# quickpi.net
KiCad netlist of a schematic drawn in EAGLE
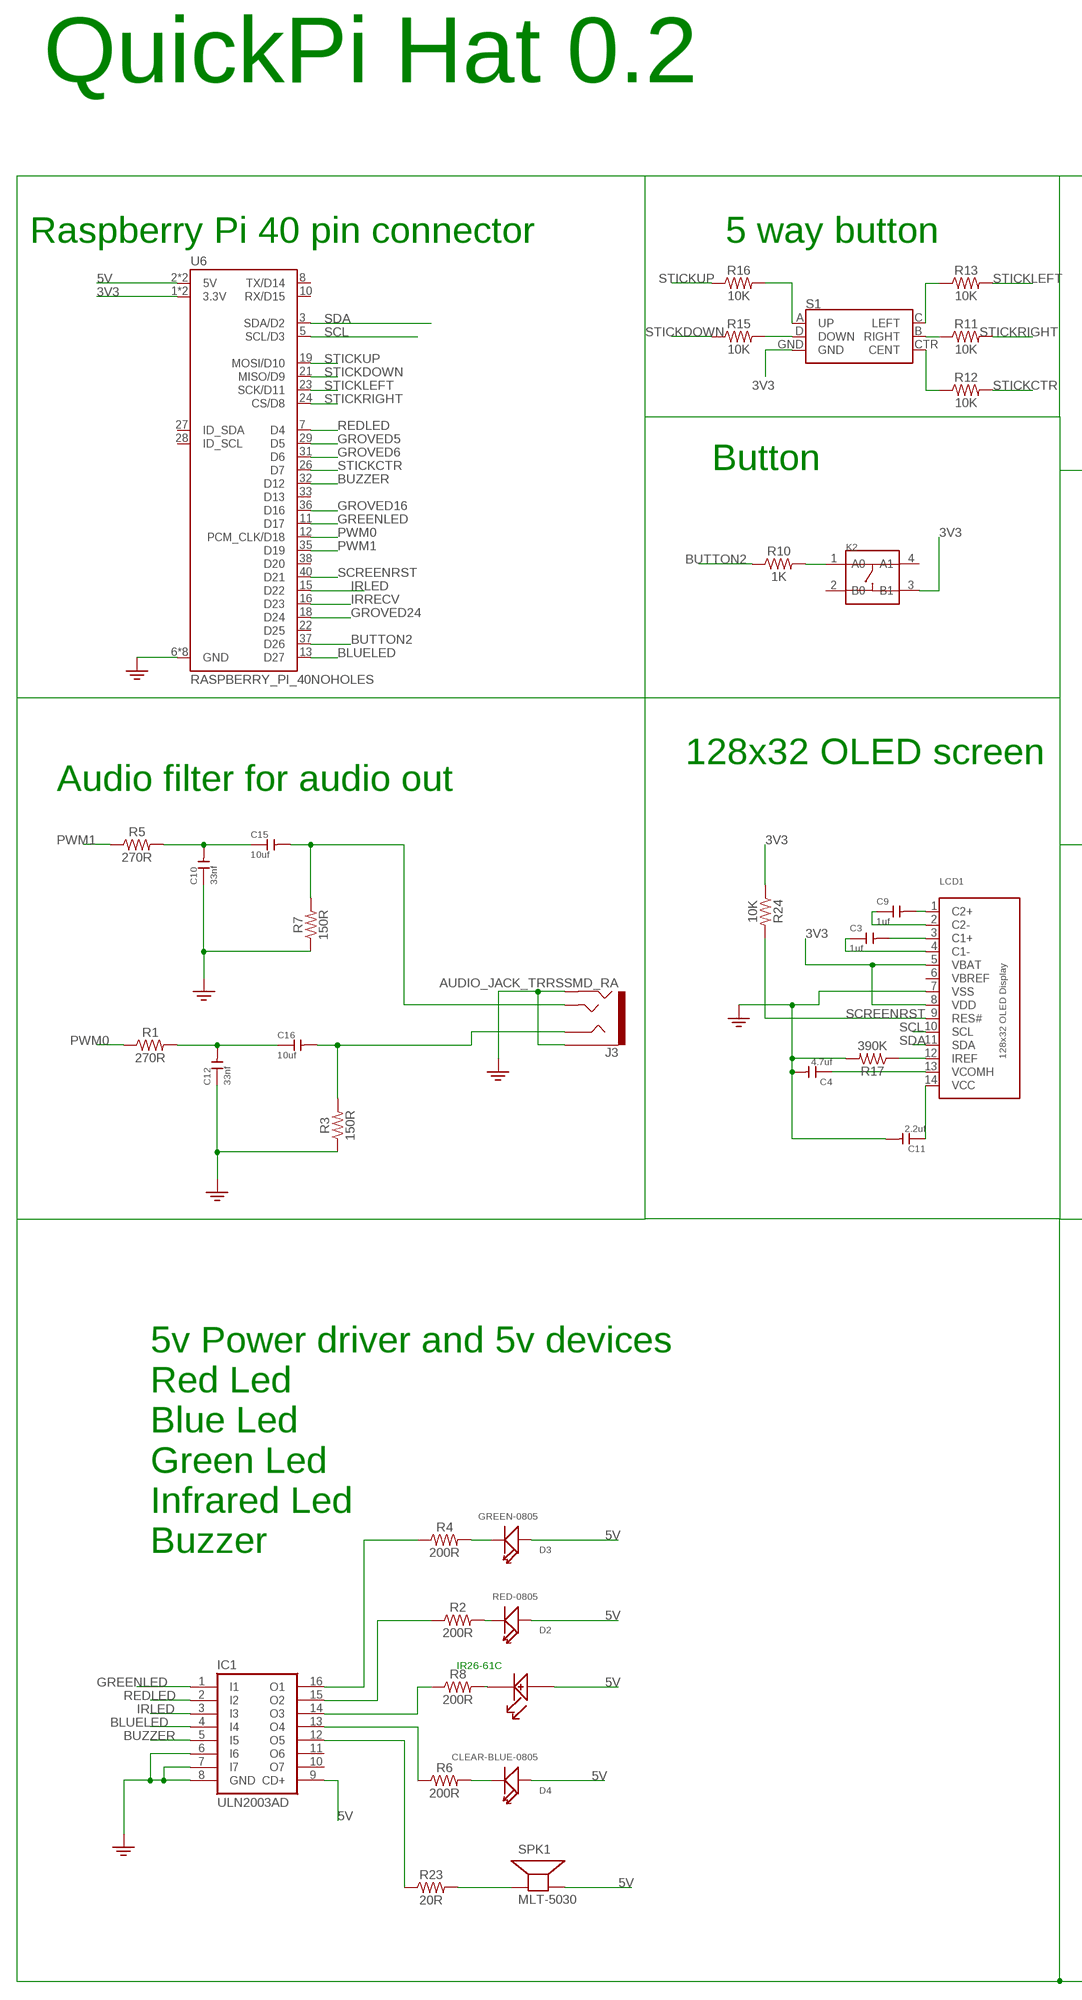
[diagram p0: schematic, sheet 1, part 1 of 2]
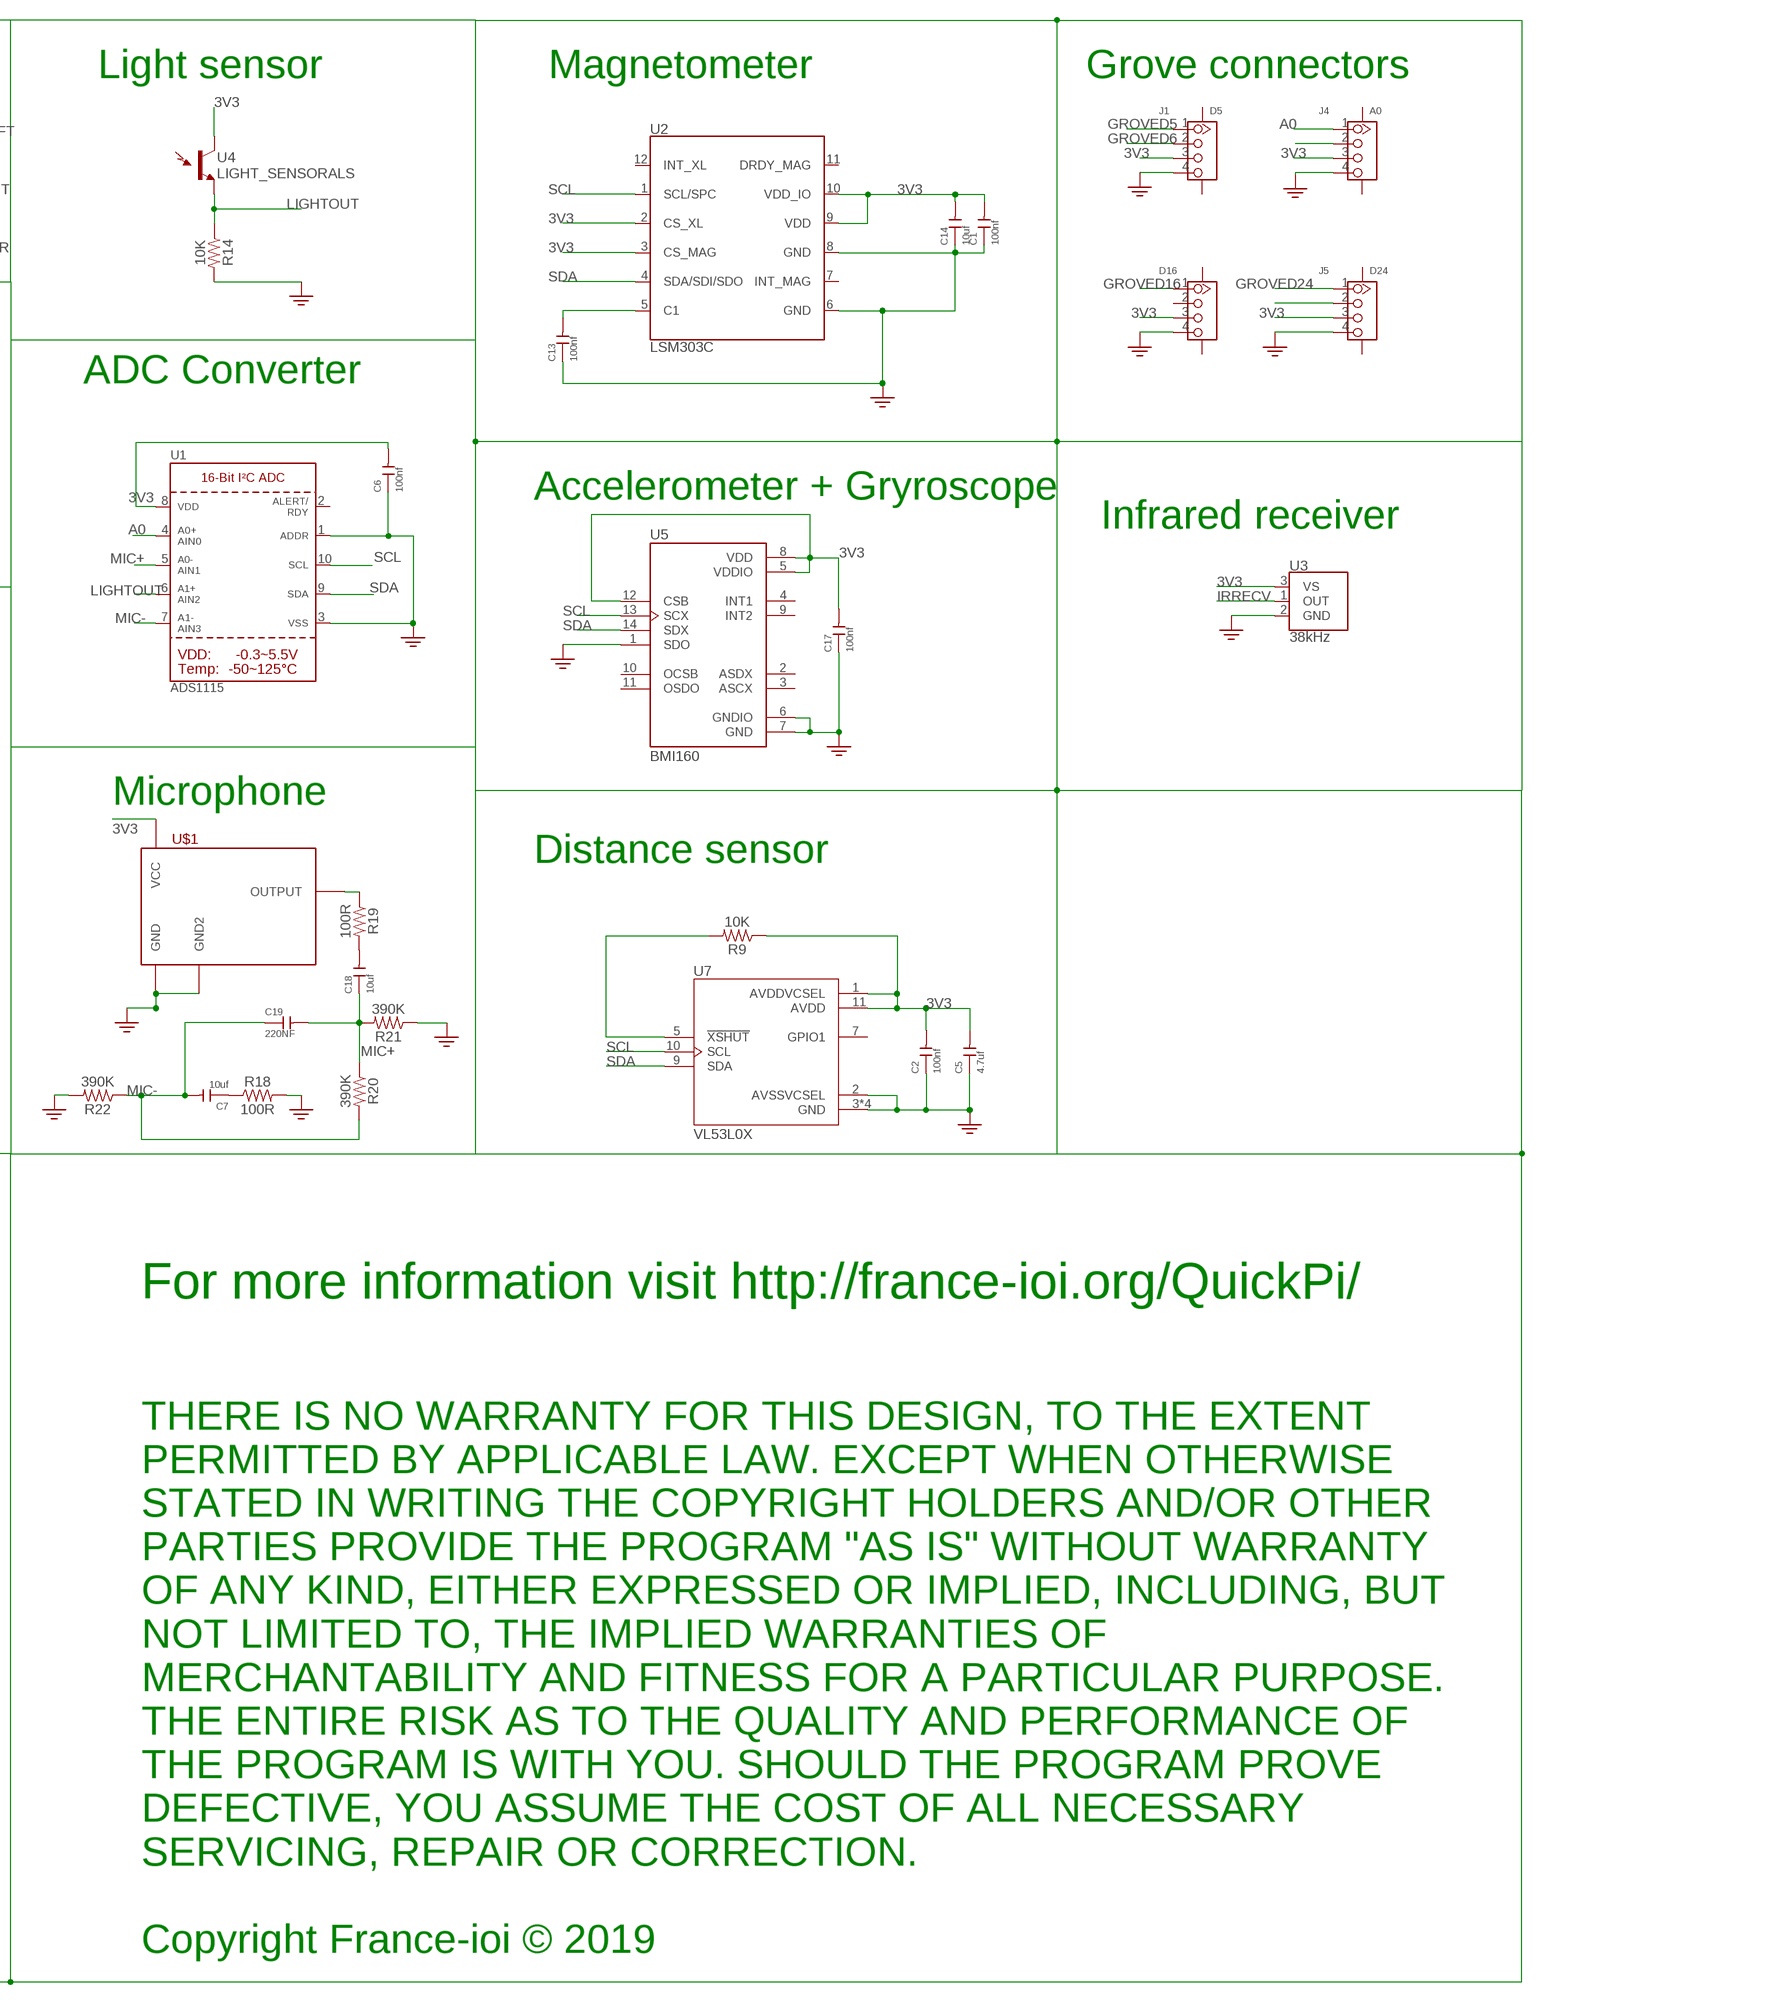
[diagram p1: schematic, sheet 1, part 2 of 2]

(export (version "E")
  (design (tool "Eeschema 10.0.6"))
  (components
    (comp (ref "C1")
      (value "100nf")
      (footprint "eagle-import:C0402")
      (fields (field (name "MPN") "CC0402KRX7R8BB104"))
      (libsource (lib "eagle-import") (part "CERAMIC-100NF-25V-10%-X7R(0402)"))
    )
    (comp (ref "C2")
      (value "100nf")
      (footprint "eagle-import:C0402")
      (fields (field (name "MPN") "CC0402KRX7R8BB104"))
      (libsource (lib "eagle-import") (part "CERAMIC-100NF-25V-10%-X7R(0402)"))
    )
    (comp (ref "C3")
      (value "1uf")
      (footprint "eagle-import:C0402")
      (fields (field (name "MPN") "CC0402KRX5R6BB105"))
      (libsource (lib "eagle-import") (part "CERAMIC-1UF-10V-10%-X5R(0402)"))
    )
    (comp (ref "C4")
      (value "4.7uf")
      (footprint "eagle-import:C0402")
      (fields (field (name "MPN") "CC0402MRX5R5BB475"))
      (libsource (lib "eagle-import") (part "CERAMIC-4.7UF-6.3V-20%-X5R(0402)"))
    )
    (comp (ref "C5")
      (value "4.7uf")
      (footprint "eagle-import:C0402")
      (fields (field (name "MPN") "CC0402MRX5R5BB475"))
      (libsource (lib "eagle-import") (part "CERAMIC-4.7UF-6.3V-20%-X5R(0402)"))
    )
    (comp (ref "C6")
      (value "100nf")
      (footprint "eagle-import:C0402")
      (fields (field (name "MPN") "CC0402KRX7R8BB104"))
      (libsource (lib "eagle-import") (part "CERAMIC-100NF-25V-10%-X7R(0402)"))
    )
    (comp (ref "C7")
      (value "10uf")
      (footprint "eagle-import:C0402")
      (fields (field (name "MPN") "CC0402KRX5R6BB105"))
      (libsource (lib "eagle-import") (part "CERAMIC-1UF-10V-10%-X5R(0402)"))
    )
    (comp (ref "C9")
      (value "1uf")
      (footprint "eagle-import:C0402")
      (fields (field (name "MPN") "CC0402KRX5R6BB105"))
      (libsource (lib "eagle-import") (part "CERAMIC-1UF-10V-10%-X5R(0402)"))
    )
    (comp (ref "C10")
      (value "33nf")
      (footprint "eagle-import:C0402")
      (fields (field (name "MPN") "CC0402MRX5R5BB106"))
      (libsource (lib "eagle-import") (part "CERAMIC-10UF-6.3V-20%-X5R(0402)"))
    )
    (comp (ref "C11")
      (value "2.2uf")
      (footprint "eagle-import:C0402")
      (fields (field (name "MPN") "CC0402MRX5R5BB475"))
      (libsource (lib "eagle-import") (part "CERAMIC-4.7UF-6.3V-20%-X5R(0402)"))
    )
    (comp (ref "C12")
      (value "33nf")
      (footprint "eagle-import:C0402")
      (fields (field (name "MPN") "CC0402MRX5R5BB106"))
      (libsource (lib "eagle-import") (part "CERAMIC-10UF-6.3V-20%-X5R(0402)"))
    )
    (comp (ref "C13")
      (value "100nf")
      (footprint "eagle-import:C0402")
      (fields (field (name "MPN") "CC0402KRX7R8BB104"))
      (libsource (lib "eagle-import") (part "CERAMIC-100NF-25V-10%-X7R(0402)"))
    )
    (comp (ref "C14")
      (value "10uf")
      (footprint "eagle-import:C0402")
      (fields (field (name "MPN") "CC0402MRX5R5BB106"))
      (libsource (lib "eagle-import") (part "CERAMIC-10UF-6.3V-20%-X5R(0402)"))
    )
    (comp (ref "C15")
      (value "10uf")
      (footprint "eagle-import:C0402")
      (fields (field (name "MPN") "CC0402MRX5R5BB106"))
      (libsource (lib "eagle-import") (part "CERAMIC-10UF-6.3V-20%-X5R(0402)"))
    )
    (comp (ref "C16")
      (value "10uf")
      (footprint "eagle-import:C0402")
      (fields (field (name "MPN") "CC0402MRX5R5BB106"))
      (libsource (lib "eagle-import") (part "CERAMIC-10UF-6.3V-20%-X5R(0402)"))
    )
    (comp (ref "C17")
      (value "100nf")
      (footprint "eagle-import:C0402")
      (fields (field (name "MPN") "CC0402KRX7R8BB104"))
      (libsource (lib "eagle-import") (part "CERAMIC-100NF-25V-10%-X7R(0402)"))
    )
    (comp (ref "C18")
      (value "10uf")
      (footprint "eagle-import:C0402")
      (fields (field (name "MPN") "CC0402KRX5R6BB105"))
      (libsource (lib "eagle-import") (part "CERAMIC-1UF-10V-10%-X5R(0402)"))
    )
    (comp (ref "C19")
      (value "220NF")
      (footprint "eagle-import:C0402")
      (fields (field (name "MPN") "CC0402KRX7R7BB224"))
      (libsource (lib "eagle-import") (part "CERAMIC-220NF-16V-10%-X7R(0402)"))
    )
    (comp (ref "D2")
      (value "RED-0805")
      (footprint "eagle-import:LED-0805")
      (fields (field (name "MPN") "17-215SURC/S530-A2/TR8"))
      (libsource (lib "eagle-import") (part "SMD-LED-CLEAR-RED(0805)"))
    )
    (comp (ref "D3")
      (value "GREEN-0805")
      (footprint "eagle-import:LED-0805")
      (fields (field (name "MPN") "17-215SYGC/S530-E2/TR8"))
      (libsource (lib "eagle-import") (part "SMD-LED-CLEAR-GREEN(0805)"))
    )
    (comp (ref "D4")
      (value "CLEAR-BLUE-0805")
      (footprint "eagle-import:LED-0805")
      (fields (field (name "MPN") "EL-17-215/BHC-AN1P2/3T"))
      (libsource (lib "eagle-import") (part "SMD-LED-CLEAR-BLUE(0805)"))
    )
    (comp (ref "D16")
      (value "GROVE-CONNECTOR-SMD-90D(4+2P-2.0)")
      (footprint "eagle-import:HW4-SMD-2.0-90D")
      (libsource (lib "eagle-import") (part "GROVE-CONNECTOR-SMD-90D(4+2P-2.0)"))
    )
    (comp (ref "IC1")
      (value "ULN2003AD")
      (footprint "eagle-import:SO16")
      (libsource (lib "eagle-import") (part "ULN2003AD"))
    )
    (comp (ref "J1")
      (value "D5")
      (footprint "eagle-import:HW4-SMD-2.0-90D")
      (libsource (lib "eagle-import") (part "GROVE-CONNECTOR-SMD-90D(4+2P-2.0)"))
    )
    (comp (ref "J3")
      (value "AUDIO_JACK_TRRSSMD_RA")
      (footprint "eagle-import:AUDIO_JACK_3.5MM_TRRS_SMD_RA")
      (libsource (lib "eagle-import") (part "AUDIO_JACK_TRRSSMD_RA"))
    )
    (comp (ref "J4")
      (value "A0")
      (footprint "eagle-import:HW4-SMD-2.0-90D")
      (libsource (lib "eagle-import") (part "GROVE-CONNECTOR-SMD-90D(4+2P-2.0)"))
    )
    (comp (ref "J5")
      (value "D24")
      (footprint "eagle-import:HW4-SMD-2.0-90D")
      (libsource (lib "eagle-import") (part "GROVE-CONNECTOR-SMD-90D(4+2P-2.0)"))
    )
    (comp (ref "K2")
      (value "SMD-SWITCH-TACTILE-SPST-NO(4P-D6.0MM)")
      (footprint "eagle-import:SW4-SMD-6.0X6.0X5.0MM")
      (fields (field (name "MPN") "DTSM-62K-S-V-T/R(SN431)"))
      (libsource (lib "eagle-import") (part "SMD-SWITCH-TACTILE-SPST-NO(4P-D6.0MM)"))
    )
    (comp (ref "LCD1")
      (value "DISP_OLED_UG-2832HSWEG02")
      (footprint "eagle-import:UG-2832HSWEG02_WRAPUNDER")
      (libsource (lib "eagle-import") (part "DISP_OLED_UG-2832HSWEG02"))
    )
    (comp (ref "R1")
      (value "270R")
      (footprint "eagle-import:0402")
      (libsource (lib "eagle-import") (part "RESISTOR0402"))
    )
    (comp (ref "R2")
      (value "200R")
      (footprint "eagle-import:0402")
      (libsource (lib "eagle-import") (part "RESISTOR0402"))
    )
    (comp (ref "R3")
      (value "150R")
      (footprint "eagle-import:0402")
      (libsource (lib "eagle-import") (part "RESISTOR0402"))
    )
    (comp (ref "R4")
      (value "200R")
      (footprint "eagle-import:0402")
      (libsource (lib "eagle-import") (part "RESISTOR0402"))
    )
    (comp (ref "R5")
      (value "270R")
      (footprint "eagle-import:0402")
      (libsource (lib "eagle-import") (part "RESISTOR0402"))
    )
    (comp (ref "R6")
      (value "200R")
      (footprint "eagle-import:0402")
      (libsource (lib "eagle-import") (part "RESISTOR0402"))
    )
    (comp (ref "R7")
      (value "150R")
      (footprint "eagle-import:0402")
      (libsource (lib "eagle-import") (part "RESISTOR0402"))
    )
    (comp (ref "R8")
      (value "200R")
      (footprint "eagle-import:0402")
      (libsource (lib "eagle-import") (part "RESISTOR0402"))
    )
    (comp (ref "R9")
      (value "10K")
      (footprint "eagle-import:0402")
      (libsource (lib "eagle-import") (part "RESISTOR0402"))
    )
    (comp (ref "R10")
      (value "1K")
      (footprint "eagle-import:0402")
      (libsource (lib "eagle-import") (part "RESISTOR0402"))
    )
    (comp (ref "R11")
      (value "10K")
      (footprint "eagle-import:0402")
      (libsource (lib "eagle-import") (part "RESISTOR0402"))
    )
    (comp (ref "R12")
      (value "10K")
      (footprint "eagle-import:0402")
      (libsource (lib "eagle-import") (part "RESISTOR0402"))
    )
    (comp (ref "R13")
      (value "10K")
      (footprint "eagle-import:0402")
      (libsource (lib "eagle-import") (part "RESISTOR0402"))
    )
    (comp (ref "R14")
      (value "10K")
      (footprint "eagle-import:0402")
      (libsource (lib "eagle-import") (part "RESISTOR0402"))
    )
    (comp (ref "R15")
      (value "10K")
      (footprint "eagle-import:0402")
      (libsource (lib "eagle-import") (part "RESISTOR0402"))
    )
    (comp (ref "R16")
      (value "10K")
      (footprint "eagle-import:0402")
      (libsource (lib "eagle-import") (part "RESISTOR0402"))
    )
    (comp (ref "R17")
      (value "390K")
      (footprint "eagle-import:0402")
      (libsource (lib "eagle-import") (part "RESISTOR0402"))
    )
    (comp (ref "R18")
      (value "100R")
      (footprint "eagle-import:0402")
      (libsource (lib "eagle-import") (part "RESISTOR0402"))
    )
    (comp (ref "R19")
      (value "100R")
      (footprint "eagle-import:0402")
      (libsource (lib "eagle-import") (part "RESISTOR0402"))
    )
    (comp (ref "R20")
      (value "390K")
      (footprint "eagle-import:0402")
      (libsource (lib "eagle-import") (part "RESISTOR0402"))
    )
    (comp (ref "R21")
      (value "390K")
      (footprint "eagle-import:0402")
      (libsource (lib "eagle-import") (part "RESISTOR0402"))
    )
    (comp (ref "R22")
      (value "390K")
      (footprint "eagle-import:0402")
      (libsource (lib "eagle-import") (part "RESISTOR0402"))
    )
    (comp (ref "R23")
      (value "20R")
      (footprint "eagle-import:0402")
      (libsource (lib "eagle-import") (part "RESISTOR0402"))
    )
    (comp (ref "R24")
      (value "10K")
      (footprint "eagle-import:0402")
      (libsource (lib "eagle-import") (part "RESISTOR0402"))
    )
    (comp (ref "S1")
      (value "JOYSTICK_MINI")
      (footprint "eagle-import:JOYSTICK_MINI")
      (libsource (lib "eagle-import") (part "JOYSTICK_MINI"))
    )
    (comp (ref "SPK1")
      (value "MLT-5030")
      (footprint "eagle-import:SMT-0540-S-R")
      (libsource (lib "eagle-import") (part "SMT-0540-S-R"))
    )
    (comp (ref "U$1")
      (value "MEMS_MIC_SPU0414HR5H-SB")
      (footprint "eagle-import:CSP-4PIN")
      (libsource (lib "eagle-import") (part "MEMS_MIC_SPU0414HR5H-SB"))
    )
    (comp (ref "U$2")
      (value "IR26-61C/L302/TR8")
      (footprint "eagle-import:IR26-61C_L302_TR8")
      (libsource (lib "eagle-import") (part "IR26-61C/L302/TR8"))
    )
    (comp (ref "U1")
      (value "ADS1015")
      (footprint "eagle-import:MSOP10")
      (fields (field (name "MF") "Texas Instruments") (field (name "MP") "ADS1115"))
      (libsource (lib "eagle-import") (part "ADS1115"))
    )
    (comp (ref "U2")
      (value "LSM303C")
      (footprint "eagle-import:LGA-12")
      (libsource (lib "eagle-import") (part "LSM303C"))
    )
    (comp (ref "U3")
      (value "38kHz")
      (footprint "eagle-import:TSOP382")
      (libsource (lib "eagle-import") (part "TSOP38238"))
    )
    (comp (ref "U4")
      (value "LIGHT_SENSORALS")
      (footprint "eagle-import:ALS-PT19")
      (libsource (lib "eagle-import") (part "LIGHT_SENSORALS"))
    )
    (comp (ref "U5")
      (value "BMI160")
      (footprint "eagle-import:PQFN50P300X250X88-14N")
      (fields (field (name "MF") "Bosch"))
      (libsource (lib "eagle-import") (part "BMI160"))
    )
    (comp (ref "U6")
      (value "RASPBERRY_PI_40NOHOLES")
      (footprint "eagle-import:RASPBERRY_PI_SHIELD_NOHOLES")
      (libsource (lib "eagle-import") (part "RASPBERRY_PI_40NOHOLES"))
    )
    (comp (ref "U7")
      (value "VL53L0X")
      (footprint "eagle-import:SENSOR_VL53L0X")
      (fields (field (name "MF") "STMicroelectronics"))
      (libsource (lib "eagle-import") (part "VL53L0X"))
    )
  )
  (nets
    (net (code "1") (name "/3V3") (class "Default")
      (node (ref "C1") (pin "2") (pinfunction "2_2") (pintype "passive"))
      (node (ref "C14") (pin "2") (pinfunction "2_2") (pintype "passive"))
      (node (ref "C17") (pin "2") (pinfunction "2_2") (pintype "passive"))
      (node (ref "C2") (pin "2") (pinfunction "2_2") (pintype "passive"))
      (node (ref "C5") (pin "2") (pinfunction "2_2") (pintype "passive"))
      (node (ref "C6") (pin "2") (pinfunction "2_2") (pintype "passive"))
      (node (ref "D16") (pin "3") (pinfunction "3_3") (pintype "bidirectional"))
      (node (ref "J1") (pin "3") (pinfunction "3_3") (pintype "bidirectional"))
      (node (ref "J4") (pin "3") (pinfunction "3_3") (pintype "bidirectional"))
      (node (ref "J5") (pin "3") (pinfunction "3_3") (pintype "bidirectional"))
      (node (ref "K2") (pin "3") (pinfunction "B1_3") (pintype "bidirectional"))
      (node (ref "LCD1") (pin "5") (pinfunction "VBAT_5") (pintype "power_in"))
      (node (ref "LCD1") (pin "8") (pinfunction "VDD_8") (pintype "power_in"))
      (node (ref "R24") (pin "1") (pinfunction "1_1") (pintype "passive"))
      (node (ref "R9") (pin "1") (pinfunction "1_1") (pintype "passive"))
      (node (ref "S1") (pin "GND") (pinfunction "GND_GND") (pintype "bidirectional"))
      (node (ref "U$1") (pin "VCC") (pinfunction "VCC_VCC") (pintype "bidirectional"))
      (node (ref "U1") (pin "8") (pinfunction "VDD_8") (pintype "bidirectional"))
      (node (ref "U2") (pin "10") (pinfunction "VDD_IO_10") (pintype "bidirectional"))
      (node (ref "U2") (pin "2") (pinfunction "CS_XL_2") (pintype "bidirectional"))
      (node (ref "U2") (pin "3") (pinfunction "CS_MAG_3") (pintype "bidirectional"))
      (node (ref "U2") (pin "9") (pinfunction "VDD_9") (pintype "bidirectional"))
      (node (ref "U3") (pin "3") (pinfunction "VS_3") (pintype "bidirectional"))
      (node (ref "U4") (pin "C") (pinfunction "C1_C") (pintype "passive"))
      (node (ref "U5") (pin "12") (pinfunction "CSB_12") (pintype "input"))
      (node (ref "U5") (pin "5") (pinfunction "VDDIO_5") (pintype "power_in"))
      (node (ref "U5") (pin "8") (pinfunction "VDD_8") (pintype "power_in"))
      (node (ref "U6") (pin "1") (pinfunction "3.3V_1") (pintype "bidirectional"))
      (node (ref "U6") (pin "17") (pinfunction "3.3V_17") (pintype "bidirectional"))
      (node (ref "U7") (pin "1") (pinfunction "AVDDVCSEL_1") (pintype "power_in"))
      (node (ref "U7") (pin "11") (pinfunction "AVDD_11") (pintype "power_in"))
    )
    (net (code "2") (name "/5V") (class "Default")
      (node (ref "D2") (pin "+") (pinfunction "+_+") (pintype "passive"))
      (node (ref "D3") (pin "+") (pinfunction "+_+") (pintype "passive"))
      (node (ref "D4") (pin "+") (pinfunction "+_+") (pintype "passive"))
      (node (ref "IC1") (pin "9") (pinfunction "CD+_9") (pintype "passive"))
      (node (ref "SPK1") (pin "+") (pinfunction "-_+") (pintype "passive"))
      (node (ref "U$2") (pin "VCC") (pinfunction "GND_VCC") (pintype "bidirectional"))
      (node (ref "U6") (pin "2") (pinfunction "5V_2") (pintype "bidirectional"))
      (node (ref "U6") (pin "4") (pinfunction "5V_4") (pintype "bidirectional"))
    )
    (net (code "3") (name "/A0") (class "Default")
      (node (ref "J4") (pin "1") (pinfunction "1_1") (pintype "bidirectional"))
      (node (ref "U1") (pin "4") (pinfunction "AIN0_4") (pintype "bidirectional"))
    )
    (net (code "4") (name "/BLUELED") (class "Default")
      (node (ref "IC1") (pin "4") (pinfunction "I4_4") (pintype "input"))
      (node (ref "U6") (pin "13") (pinfunction "D27_13") (pintype "bidirectional"))
    )
    (net (code "5") (name "/BUTTON2") (class "Default")
      (node (ref "R10") (pin "1") (pinfunction "1_1") (pintype "passive"))
      (node (ref "U6") (pin "37") (pinfunction "D26_37") (pintype "bidirectional"))
    )
    (net (code "6") (name "/BUZZER") (class "Default")
      (node (ref "IC1") (pin "5") (pinfunction "I5_5") (pintype "input"))
      (node (ref "U6") (pin "32") (pinfunction "D12_32") (pintype "bidirectional"))
    )
    (net (code "7") (name "/GREENLED") (class "Default")
      (node (ref "IC1") (pin "1") (pinfunction "I1_1") (pintype "input"))
      (node (ref "U6") (pin "11") (pinfunction "D17_11") (pintype "bidirectional"))
    )
    (net (code "8") (name "/GROVED5") (class "Default")
      (node (ref "J1") (pin "1") (pinfunction "1_1") (pintype "bidirectional"))
      (node (ref "U6") (pin "29") (pinfunction "D5_29") (pintype "bidirectional"))
    )
    (net (code "9") (name "/GROVED6") (class "Default")
      (node (ref "J1") (pin "2") (pinfunction "2_2") (pintype "bidirectional"))
      (node (ref "U6") (pin "31") (pinfunction "D6_31") (pintype "bidirectional"))
    )
    (net (code "10") (name "/GROVED16") (class "Default")
      (node (ref "D16") (pin "1") (pinfunction "1_1") (pintype "bidirectional"))
      (node (ref "U6") (pin "36") (pinfunction "D16_36") (pintype "bidirectional"))
    )
    (net (code "11") (name "/GROVED24") (class "Default")
      (node (ref "J5") (pin "1") (pinfunction "1_1") (pintype "bidirectional"))
      (node (ref "U6") (pin "18") (pinfunction "D24_18") (pintype "bidirectional"))
    )
    (net (code "12") (name "/IRLED") (class "Default")
      (node (ref "IC1") (pin "3") (pinfunction "I3_3") (pintype "input"))
      (node (ref "U6") (pin "15") (pinfunction "D22_15") (pintype "bidirectional"))
    )
    (net (code "13") (name "/IRRECV") (class "Default")
      (node (ref "U3") (pin "1") (pinfunction "OUT_1") (pintype "bidirectional"))
      (node (ref "U6") (pin "16") (pinfunction "D23_16") (pintype "bidirectional"))
    )
    (net (code "14") (name "/LIGHTOUT") (class "Default")
      (node (ref "R14") (pin "1") (pinfunction "1_1") (pintype "passive"))
      (node (ref "U1") (pin "6") (pinfunction "AIN2_6") (pintype "bidirectional"))
      (node (ref "U4") (pin "E") (pinfunction "E1_E") (pintype "passive"))
    )
    (net (code "15") (name "/MIC+") (class "Default")
      (node (ref "C18") (pin "1") (pinfunction "1_1") (pintype "passive"))
      (node (ref "C19") (pin "2") (pinfunction "2_2") (pintype "passive"))
      (node (ref "R20") (pin "1") (pinfunction "1_1") (pintype "passive"))
      (node (ref "R21") (pin "2") (pinfunction "2_2") (pintype "passive"))
      (node (ref "U1") (pin "5") (pinfunction "AIN1_5") (pintype "bidirectional"))
    )
    (net (code "16") (name "/MIC-") (class "Default")
      (node (ref "C19") (pin "1") (pinfunction "1_1") (pintype "passive"))
      (node (ref "C7") (pin "2") (pinfunction "2_2") (pintype "passive"))
      (node (ref "R20") (pin "2") (pinfunction "2_2") (pintype "passive"))
      (node (ref "R22") (pin "1") (pinfunction "1_1") (pintype "passive"))
      (node (ref "U1") (pin "7") (pinfunction "AIN3_7") (pintype "bidirectional"))
    )
    (net (code "17") (name "/PWM0") (class "Default")
      (node (ref "R1") (pin "1") (pinfunction "1_1") (pintype "passive"))
      (node (ref "U6") (pin "12") (pinfunction "PCM_CLK/D18_12") (pintype "bidirectional"))
    )
    (net (code "18") (name "/PWM1") (class "Default")
      (node (ref "R5") (pin "1") (pinfunction "1_1") (pintype "passive"))
      (node (ref "U6") (pin "35") (pinfunction "D19_35") (pintype "bidirectional"))
    )
    (net (code "19") (name "/REDLED") (class "Default")
      (node (ref "IC1") (pin "2") (pinfunction "I2_2") (pintype "input"))
      (node (ref "U6") (pin "7") (pinfunction "D4_7") (pintype "bidirectional"))
    )
    (net (code "20") (name "/SCL") (class "Default")
      (node (ref "LCD1") (pin "10") (pinfunction "SCL_10") (pintype "bidirectional"))
      (node (ref "U1") (pin "10") (pinfunction "SCL_10") (pintype "bidirectional"))
      (node (ref "U2") (pin "1") (pinfunction "SCL/SPC_1") (pintype "bidirectional"))
      (node (ref "U5") (pin "13") (pinfunction "SCX_13") (pintype "input"))
      (node (ref "U6") (pin "5") (pinfunction "SCL/D3_5") (pintype "bidirectional"))
      (node (ref "U7") (pin "10") (pinfunction "SCL_10") (pintype "input"))
    )
    (net (code "21") (name "/SCREENRST") (class "Default")
      (node (ref "LCD1") (pin "9") (pinfunction "RES#_9") (pintype "bidirectional"))
      (node (ref "R24") (pin "2") (pinfunction "2_2") (pintype "passive"))
      (node (ref "U6") (pin "40") (pinfunction "D21_40") (pintype "bidirectional"))
    )
    (net (code "22") (name "/SDA") (class "Default")
      (node (ref "LCD1") (pin "11") (pinfunction "SDA_11") (pintype "bidirectional"))
      (node (ref "U1") (pin "9") (pinfunction "SDA_9") (pintype "bidirectional"))
      (node (ref "U2") (pin "4") (pinfunction "SDA/SDI/SDO_4") (pintype "bidirectional"))
      (node (ref "U5") (pin "14") (pinfunction "SDX_14") (pintype "bidirectional"))
      (node (ref "U6") (pin "3") (pinfunction "SDA/D2_3") (pintype "bidirectional"))
      (node (ref "U7") (pin "9") (pinfunction "SDA_9") (pintype "bidirectional"))
    )
    (net (code "23") (name "/STICKCTR") (class "Default")
      (node (ref "R12") (pin "2") (pinfunction "2_2") (pintype "passive"))
      (node (ref "U6") (pin "26") (pinfunction "D7_26") (pintype "bidirectional"))
    )
    (net (code "24") (name "/STICKDOWN") (class "Default")
      (node (ref "R15") (pin "1") (pinfunction "1_1") (pintype "passive"))
      (node (ref "U6") (pin "21") (pinfunction "MISO/D9_21") (pintype "bidirectional"))
    )
    (net (code "25") (name "/STICKLEFT") (class "Default")
      (node (ref "R13") (pin "2") (pinfunction "2_2") (pintype "passive"))
      (node (ref "U6") (pin "23") (pinfunction "SCK/D11_23") (pintype "bidirectional"))
    )
    (net (code "26") (name "/STICKRIGHT") (class "Default")
      (node (ref "R11") (pin "2") (pinfunction "2_2") (pintype "passive"))
      (node (ref "U6") (pin "24") (pinfunction "CS/D8_24") (pintype "bidirectional"))
    )
    (net (code "27") (name "/STICKUP") (class "Default")
      (node (ref "R16") (pin "1") (pinfunction "1_1") (pintype "passive"))
      (node (ref "U6") (pin "19") (pinfunction "MOSI/D10_19") (pintype "bidirectional"))
    )
    (net (code "28") (name "/VBREF") (class "Default")
      (node (ref "LCD1") (pin "6") (pinfunction "VBREF_6") (pintype "power_in"))
    )
    (net (code "29") (name "GND2") (class "Default")
      (node (ref "C1") (pin "1") (pinfunction "1_1") (pintype "passive"))
      (node (ref "C10") (pin "1") (pinfunction "1_1") (pintype "passive"))
      (node (ref "C11") (pin "2") (pinfunction "2_2") (pintype "passive"))
      (node (ref "C12") (pin "1") (pinfunction "1_1") (pintype "passive"))
      (node (ref "C13") (pin "1") (pinfunction "1_1") (pintype "passive"))
      (node (ref "C14") (pin "1") (pinfunction "1_1") (pintype "passive"))
      (node (ref "C17") (pin "1") (pinfunction "1_1") (pintype "passive"))
      (node (ref "C2") (pin "1") (pinfunction "1_1") (pintype "passive"))
      (node (ref "C4") (pin "2") (pinfunction "2_2") (pintype "passive"))
      (node (ref "C5") (pin "1") (pinfunction "1_1") (pintype "passive"))
      (node (ref "C6") (pin "1") (pinfunction "1_1") (pintype "passive"))
      (node (ref "D16") (pin "4") (pinfunction "4_4") (pintype "bidirectional"))
      (node (ref "IC1") (pin "6") (pinfunction "I6_6") (pintype "input"))
      (node (ref "IC1") (pin "7") (pinfunction "I7_7") (pintype "input"))
      (node (ref "IC1") (pin "8") (pinfunction "GND_8") (pintype "power_in"))
      (node (ref "J1") (pin "4") (pinfunction "4_4") (pintype "bidirectional"))
      (node (ref "J3") (pin "EARTH") (pinfunction "EARTH_EARTH") (pintype "bidirectional"))
      (node (ref "J3") (pin "RING2") (pinfunction "RING2_RING2") (pintype "bidirectional"))
      (node (ref "J4") (pin "4") (pinfunction "4_4") (pintype "bidirectional"))
      (node (ref "J5") (pin "4") (pinfunction "4_4") (pintype "bidirectional"))
      (node (ref "LCD1") (pin "7") (pinfunction "VSS_7") (pintype "power_in"))
      (node (ref "R14") (pin "2") (pinfunction "2_2") (pintype "passive"))
      (node (ref "R17") (pin "2") (pinfunction "2_2") (pintype "passive"))
      (node (ref "R18") (pin "2") (pinfunction "2_2") (pintype "passive"))
      (node (ref "R21") (pin "1") (pinfunction "1_1") (pintype "passive"))
      (node (ref "R22") (pin "2") (pinfunction "2_2") (pintype "passive"))
      (node (ref "R3") (pin "1") (pinfunction "1_1") (pintype "passive"))
      (node (ref "R7") (pin "1") (pinfunction "1_1") (pintype "passive"))
      (node (ref "U$1") (pin "GND") (pinfunction "GND_GND") (pintype "bidirectional"))
      (node (ref "U$1") (pin "GND2") (pinfunction "GND2_GND2") (pintype "bidirectional"))
      (node (ref "U1") (pin "1") (pinfunction "ADDR_1") (pintype "bidirectional"))
      (node (ref "U1") (pin "3") (pinfunction "VSS_3") (pintype "bidirectional"))
      (node (ref "U2") (pin "6") (pinfunction "GND_6") (pintype "bidirectional"))
      (node (ref "U2") (pin "8") (pinfunction "GND_8") (pintype "bidirectional"))
      (node (ref "U3") (pin "2") (pinfunction "GND_2") (pintype "bidirectional"))
      (node (ref "U5") (pin "1") (pinfunction "SDO_1") (pintype "bidirectional"))
      (node (ref "U5") (pin "6") (pinfunction "GNDIO_6") (pintype "power_in"))
      (node (ref "U5") (pin "7") (pinfunction "GND_7") (pintype "power_in"))
      (node (ref "U6") (pin "14") (pinfunction "GND_14") (pintype "bidirectional"))
      (node (ref "U6") (pin "20") (pinfunction "GND_20") (pintype "bidirectional"))
      (node (ref "U6") (pin "25") (pinfunction "GND_25") (pintype "bidirectional"))
      (node (ref "U6") (pin "30") (pinfunction "GND_30") (pintype "bidirectional"))
      (node (ref "U6") (pin "34") (pinfunction "GND_34") (pintype "bidirectional"))
      (node (ref "U6") (pin "39") (pinfunction "GND_39") (pintype "bidirectional"))
      (node (ref "U6") (pin "6") (pinfunction "GND_6") (pintype "bidirectional"))
      (node (ref "U6") (pin "9") (pinfunction "GND_9") (pintype "bidirectional"))
      (node (ref "U7") (pin "12") (pinfunction "GND_12") (pintype "power_in"))
      (node (ref "U7") (pin "2") (pinfunction "AVSSVCSEL_2") (pintype "power_in"))
      (node (ref "U7") (pin "3") (pinfunction "GND_3") (pintype "power_in"))
      (node (ref "U7") (pin "4") (pinfunction "GND_4") (pintype "power_in"))
      (node (ref "U7") (pin "6") (pinfunction "GND_6") (pintype "power_in"))
    )
    (net (code "30") (name "Net-(C7-Pad1)") (class "Default")
      (node (ref "C7") (pin "1") (pinfunction "1_1") (pintype "passive"))
      (node (ref "R18") (pin "1") (pinfunction "1_1") (pintype "passive"))
    )
    (net (code "31") (name "Net-(C10-Pad2)") (class "Default")
      (node (ref "C10") (pin "2") (pinfunction "2_2") (pintype "passive"))
      (node (ref "C15") (pin "1") (pinfunction "1_1") (pintype "passive"))
      (node (ref "R5") (pin "2") (pinfunction "2_2") (pintype "passive"))
    )
    (net (code "32") (name "Net-(C12-Pad2)") (class "Default")
      (node (ref "C12") (pin "2") (pinfunction "2_2") (pintype "passive"))
      (node (ref "C16") (pin "1") (pinfunction "1_1") (pintype "passive"))
      (node (ref "R1") (pin "2") (pinfunction "2_2") (pintype "passive"))
    )
    (net (code "33") (name "Net-(C15-Pad2)") (class "Default")
      (node (ref "C15") (pin "2") (pinfunction "2_2") (pintype "passive"))
      (node (ref "J3") (pin "TIP") (pinfunction "TIP_TIP") (pintype "bidirectional"))
      (node (ref "R7") (pin "2") (pinfunction "2_2") (pintype "passive"))
    )
    (net (code "34") (name "Net-(C16-Pad2)") (class "Default")
      (node (ref "C16") (pin "2") (pinfunction "2_2") (pintype "passive"))
      (node (ref "J3") (pin "RING1") (pinfunction "RING1_RING1") (pintype "bidirectional"))
      (node (ref "R3") (pin "2") (pinfunction "2_2") (pintype "passive"))
    )
    (net (code "35") (name "Net-(C18-Pad2)") (class "Default")
      (node (ref "C18") (pin "2") (pinfunction "2_2") (pintype "passive"))
      (node (ref "R19") (pin "2") (pinfunction "2_2") (pintype "passive"))
    )
    (net (code "36") (name "Net-(D2-Pad-)") (class "Default")
      (node (ref "D2") (pin "-") (pinfunction "-_-") (pintype "passive"))
      (node (ref "R2") (pin "2") (pinfunction "2_2") (pintype "passive"))
    )
    (net (code "37") (name "Net-(D3-Pad-)") (class "Default")
      (node (ref "D3") (pin "-") (pinfunction "-_-") (pintype "passive"))
      (node (ref "R4") (pin "2") (pinfunction "2_2") (pintype "passive"))
    )
    (net (code "38") (name "Net-(D4-Pad-)") (class "Default")
      (node (ref "D4") (pin "-") (pinfunction "-_-") (pintype "passive"))
      (node (ref "R6") (pin "2") (pinfunction "2_2") (pintype "passive"))
    )
    (net (code "39") (name "Net-(IC1-O1)") (class "Default")
      (node (ref "IC1") (pin "16") (pinfunction "O1_16") (pintype "open_collector"))
      (node (ref "R4") (pin "1") (pinfunction "1_1") (pintype "passive"))
    )
    (net (code "40") (name "Net-(IC1-O2)") (class "Default")
      (node (ref "IC1") (pin "15") (pinfunction "O2_15") (pintype "open_collector"))
      (node (ref "R2") (pin "1") (pinfunction "1_1") (pintype "passive"))
    )
    (net (code "41") (name "Net-(IC1-O3)") (class "Default")
      (node (ref "IC1") (pin "14") (pinfunction "O3_14") (pintype "open_collector"))
      (node (ref "R8") (pin "1") (pinfunction "1_1") (pintype "passive"))
    )
    (net (code "42") (name "Net-(IC1-O4)") (class "Default")
      (node (ref "IC1") (pin "13") (pinfunction "O4_13") (pintype "open_collector"))
      (node (ref "R6") (pin "1") (pinfunction "1_1") (pintype "passive"))
    )
    (net (code "43") (name "Net-(IC1-O5)") (class "Default")
      (node (ref "IC1") (pin "12") (pinfunction "O5_12") (pintype "open_collector"))
      (node (ref "R23") (pin "1") (pinfunction "1_1") (pintype "passive"))
    )
    (net (code "44") (name "Net-(K2-A0)") (class "Default")
      (node (ref "K2") (pin "1") (pinfunction "A0_1") (pintype "bidirectional"))
      (node (ref "R10") (pin "2") (pinfunction "2_2") (pintype "passive"))
    )
    (net (code "45") (name "Net-(LCD1-C1+)") (class "Default")
      (node (ref "C3") (pin "2") (pinfunction "2_2") (pintype "passive"))
      (node (ref "LCD1") (pin "3") (pinfunction "C1+_3") (pintype "bidirectional"))
    )
    (net (code "46") (name "Net-(LCD1-C1-)") (class "Default")
      (node (ref "C3") (pin "1") (pinfunction "1_1") (pintype "passive"))
      (node (ref "LCD1") (pin "4") (pinfunction "C1-_4") (pintype "bidirectional"))
    )
    (net (code "47") (name "Net-(LCD1-C2+)") (class "Default")
      (node (ref "C9") (pin "2") (pinfunction "2_2") (pintype "passive"))
      (node (ref "LCD1") (pin "1") (pinfunction "C2+_1") (pintype "bidirectional"))
    )
    (net (code "48") (name "Net-(LCD1-C2-)") (class "Default")
      (node (ref "C9") (pin "1") (pinfunction "1_1") (pintype "passive"))
      (node (ref "LCD1") (pin "2") (pinfunction "C2-_2") (pintype "bidirectional"))
    )
    (net (code "49") (name "Net-(LCD1-IREF)") (class "Default")
      (node (ref "LCD1") (pin "12") (pinfunction "IREF_12") (pintype "bidirectional"))
      (node (ref "R17") (pin "1") (pinfunction "1_1") (pintype "passive"))
    )
    (net (code "50") (name "Net-(LCD1-VCC)") (class "Default")
      (node (ref "C11") (pin "1") (pinfunction "1_1") (pintype "passive"))
      (node (ref "LCD1") (pin "14") (pinfunction "VCC_14") (pintype "power_in"))
    )
    (net (code "51") (name "Net-(LCD1-VCOMH)") (class "Default")
      (node (ref "C4") (pin "1") (pinfunction "1_1") (pintype "passive"))
      (node (ref "LCD1") (pin "13") (pinfunction "VCOMH_13") (pintype "power_in"))
    )
    (net (code "52") (name "Net-(R19-Pad1)") (class "Default")
      (node (ref "R19") (pin "1") (pinfunction "1_1") (pintype "passive"))
      (node (ref "U$1") (pin "OUTPUT") (pinfunction "OUTPUT_OUTPUT") (pintype "bidirectional"))
    )
    (net (code "53") (name "Net-(S1-CENT)") (class "Default")
      (node (ref "R12") (pin "1") (pinfunction "1_1") (pintype "passive"))
      (node (ref "S1") (pin "CTR") (pinfunction "CENT_CTR") (pintype "bidirectional"))
    )
    (net (code "54") (name "Net-(S1-DOWN)") (class "Default")
      (node (ref "R15") (pin "2") (pinfunction "2_2") (pintype "passive"))
      (node (ref "S1") (pin "D") (pinfunction "DOWN_D") (pintype "bidirectional"))
    )
    (net (code "55") (name "Net-(S1-LEFT)") (class "Default")
      (node (ref "R13") (pin "1") (pinfunction "1_1") (pintype "passive"))
      (node (ref "S1") (pin "C") (pinfunction "LEFT_C") (pintype "bidirectional"))
    )
    (net (code "56") (name "Net-(S1-RIGHT)") (class "Default")
      (node (ref "R11") (pin "1") (pinfunction "1_1") (pintype "passive"))
      (node (ref "S1") (pin "B") (pinfunction "RIGHT_B") (pintype "bidirectional"))
    )
    (net (code "57") (name "Net-(S1-UP)") (class "Default")
      (node (ref "R16") (pin "2") (pinfunction "2_2") (pintype "passive"))
      (node (ref "S1") (pin "A") (pinfunction "UP_A") (pintype "bidirectional"))
    )
    (net (code "58") (name "Net-(SPK1-+)") (class "Default")
      (node (ref "R23") (pin "2") (pinfunction "2_2") (pintype "passive"))
      (node (ref "SPK1") (pin "-") (pinfunction "+_-") (pintype "passive"))
    )
    (net (code "59") (name "Net-(U$2-VCC)") (class "Default")
      (node (ref "R8") (pin "2") (pinfunction "2_2") (pintype "passive"))
      (node (ref "U$2") (pin "GND") (pinfunction "VCC_GND") (pintype "bidirectional"))
    )
    (net (code "60") (name "Net-(U2-C1)") (class "Default")
      (node (ref "C13") (pin "2") (pinfunction "2_2") (pintype "passive"))
      (node (ref "U2") (pin "5") (pinfunction "C1_5") (pintype "bidirectional"))
    )
    (net (code "61") (name "Net-(U7-~{XSHUT})") (class "Default")
      (node (ref "R9") (pin "2") (pinfunction "2_2") (pintype "passive"))
      (node (ref "U7") (pin "5") (pinfunction "~{XSHUT}_5") (pintype "input"))
    )
    (net (code "62") (name "unconnected-(D16-Pad2)") (class "Default")
      (node (ref "D16") (pin "2") (pinfunction "2_2") (pintype "bidirectional"))
    )
    (net (code "63") (name "unconnected-(D16-PadSS1)") (class "Default")
      (node (ref "D16") (pin "SS1") (pinfunction "SS1_SS1") (pintype "bidirectional"))
    )
    (net (code "64") (name "unconnected-(D16-PadSS2)") (class "Default")
      (node (ref "D16") (pin "SS2") (pinfunction "SS2_SS2") (pintype "bidirectional"))
    )
    (net (code "65") (name "unconnected-(IC1-O6-Pad11)") (class "Default")
      (node (ref "IC1") (pin "11") (pinfunction "O6_11") (pintype "open_collector"))
    )
    (net (code "66") (name "unconnected-(IC1-O7-Pad10)") (class "Default")
      (node (ref "IC1") (pin "10") (pinfunction "O7_10") (pintype "open_collector"))
    )
    (net (code "67") (name "unconnected-(J1-PadSS1)") (class "Default")
      (node (ref "J1") (pin "SS1") (pinfunction "SS1_SS1") (pintype "bidirectional"))
    )
    (net (code "68") (name "unconnected-(J1-PadSS2)") (class "Default")
      (node (ref "J1") (pin "SS2") (pinfunction "SS2_SS2") (pintype "bidirectional"))
    )
    (net (code "69") (name "unconnected-(J4-Pad2)") (class "Default")
      (node (ref "J4") (pin "2") (pinfunction "2_2") (pintype "bidirectional"))
    )
    (net (code "70") (name "unconnected-(J4-PadSS1)") (class "Default")
      (node (ref "J4") (pin "SS1") (pinfunction "SS1_SS1") (pintype "bidirectional"))
    )
    (net (code "71") (name "unconnected-(J4-PadSS2)") (class "Default")
      (node (ref "J4") (pin "SS2") (pinfunction "SS2_SS2") (pintype "bidirectional"))
    )
    (net (code "72") (name "unconnected-(J5-Pad2)") (class "Default")
      (node (ref "J5") (pin "2") (pinfunction "2_2") (pintype "bidirectional"))
    )
    (net (code "73") (name "unconnected-(J5-PadSS1)") (class "Default")
      (node (ref "J5") (pin "SS1") (pinfunction "SS1_SS1") (pintype "bidirectional"))
    )
    (net (code "74") (name "unconnected-(J5-PadSS2)") (class "Default")
      (node (ref "J5") (pin "SS2") (pinfunction "SS2_SS2") (pintype "bidirectional"))
    )
    (net (code "75") (name "unconnected-(K2-A1-Pad4)") (class "Default")
      (node (ref "K2") (pin "4") (pinfunction "A1_4") (pintype "bidirectional"))
    )
    (net (code "76") (name "unconnected-(K2-B0-Pad2)") (class "Default")
      (node (ref "K2") (pin "2") (pinfunction "B0_2") (pintype "bidirectional"))
    )
    (net (code "77") (name "unconnected-(U1-ALERT{slash}RDY-Pad2)") (class "Default")
      (node (ref "U1") (pin "2") (pinfunction "ALERT/RDY_2") (pintype "bidirectional"))
    )
    (net (code "78") (name "unconnected-(U2-DRDY_MAG-Pad11)") (class "Default")
      (node (ref "U2") (pin "11") (pinfunction "DRDY_MAG_11") (pintype "bidirectional"))
    )
    (net (code "79") (name "unconnected-(U2-INT_MAG-Pad7)") (class "Default")
      (node (ref "U2") (pin "7") (pinfunction "INT_MAG_7") (pintype "bidirectional"))
    )
    (net (code "80") (name "unconnected-(U2-INT_XL-Pad12)") (class "Default")
      (node (ref "U2") (pin "12") (pinfunction "INT_XL_12") (pintype "bidirectional"))
    )
    (net (code "81") (name "unconnected-(U5-ASCX-Pad3)") (class "Default")
      (node (ref "U5") (pin "3") (pinfunction "ASCX_3") (pintype "output"))
    )
    (net (code "82") (name "unconnected-(U5-ASDX-Pad2)") (class "Default")
      (node (ref "U5") (pin "2") (pinfunction "ASDX_2") (pintype "bidirectional"))
    )
    (net (code "83") (name "unconnected-(U5-INT1-Pad4)") (class "Default")
      (node (ref "U5") (pin "4") (pinfunction "INT1_4") (pintype "bidirectional"))
    )
    (net (code "84") (name "unconnected-(U5-INT2-Pad9)") (class "Default")
      (node (ref "U5") (pin "9") (pinfunction "INT2_9") (pintype "bidirectional"))
    )
    (net (code "85") (name "unconnected-(U5-OCSB-Pad10)") (class "Default")
      (node (ref "U5") (pin "10") (pinfunction "OCSB_10") (pintype "bidirectional"))
    )
    (net (code "86") (name "unconnected-(U5-OSDO-Pad11)") (class "Default")
      (node (ref "U5") (pin "11") (pinfunction "OSDO_11") (pintype "bidirectional"))
    )
    (net (code "87") (name "unconnected-(U6-D13-Pad33)") (class "Default")
      (node (ref "U6") (pin "33") (pinfunction "D13_33") (pintype "bidirectional"))
    )
    (net (code "88") (name "unconnected-(U6-D20-Pad38)") (class "Default")
      (node (ref "U6") (pin "38") (pinfunction "D20_38") (pintype "bidirectional"))
    )
    (net (code "89") (name "unconnected-(U6-D25-Pad22)") (class "Default")
      (node (ref "U6") (pin "22") (pinfunction "D25_22") (pintype "bidirectional"))
    )
    (net (code "90") (name "unconnected-(U6-ID_SCL-Pad28)") (class "Default")
      (node (ref "U6") (pin "28") (pinfunction "ID_SCL_28") (pintype "bidirectional"))
    )
    (net (code "91") (name "unconnected-(U6-ID_SDA-Pad27)") (class "Default")
      (node (ref "U6") (pin "27") (pinfunction "ID_SDA_27") (pintype "bidirectional"))
    )
    (net (code "92") (name "unconnected-(U6-RX{slash}D15-Pad10)") (class "Default")
      (node (ref "U6") (pin "10") (pinfunction "RX/D15_10") (pintype "bidirectional"))
    )
    (net (code "93") (name "unconnected-(U6-TX{slash}D14-Pad8)") (class "Default")
      (node (ref "U6") (pin "8") (pinfunction "TX/D14_8") (pintype "bidirectional"))
    )
    (net (code "94") (name "unconnected-(U7-GPIO1-Pad7)") (class "Default")
      (node (ref "U7") (pin "7") (pinfunction "GPIO1_7") (pintype "output"))
    )
  )
)
